# kontrol_v2.net
KiCad netlist of a schematic drawn in EAGLE
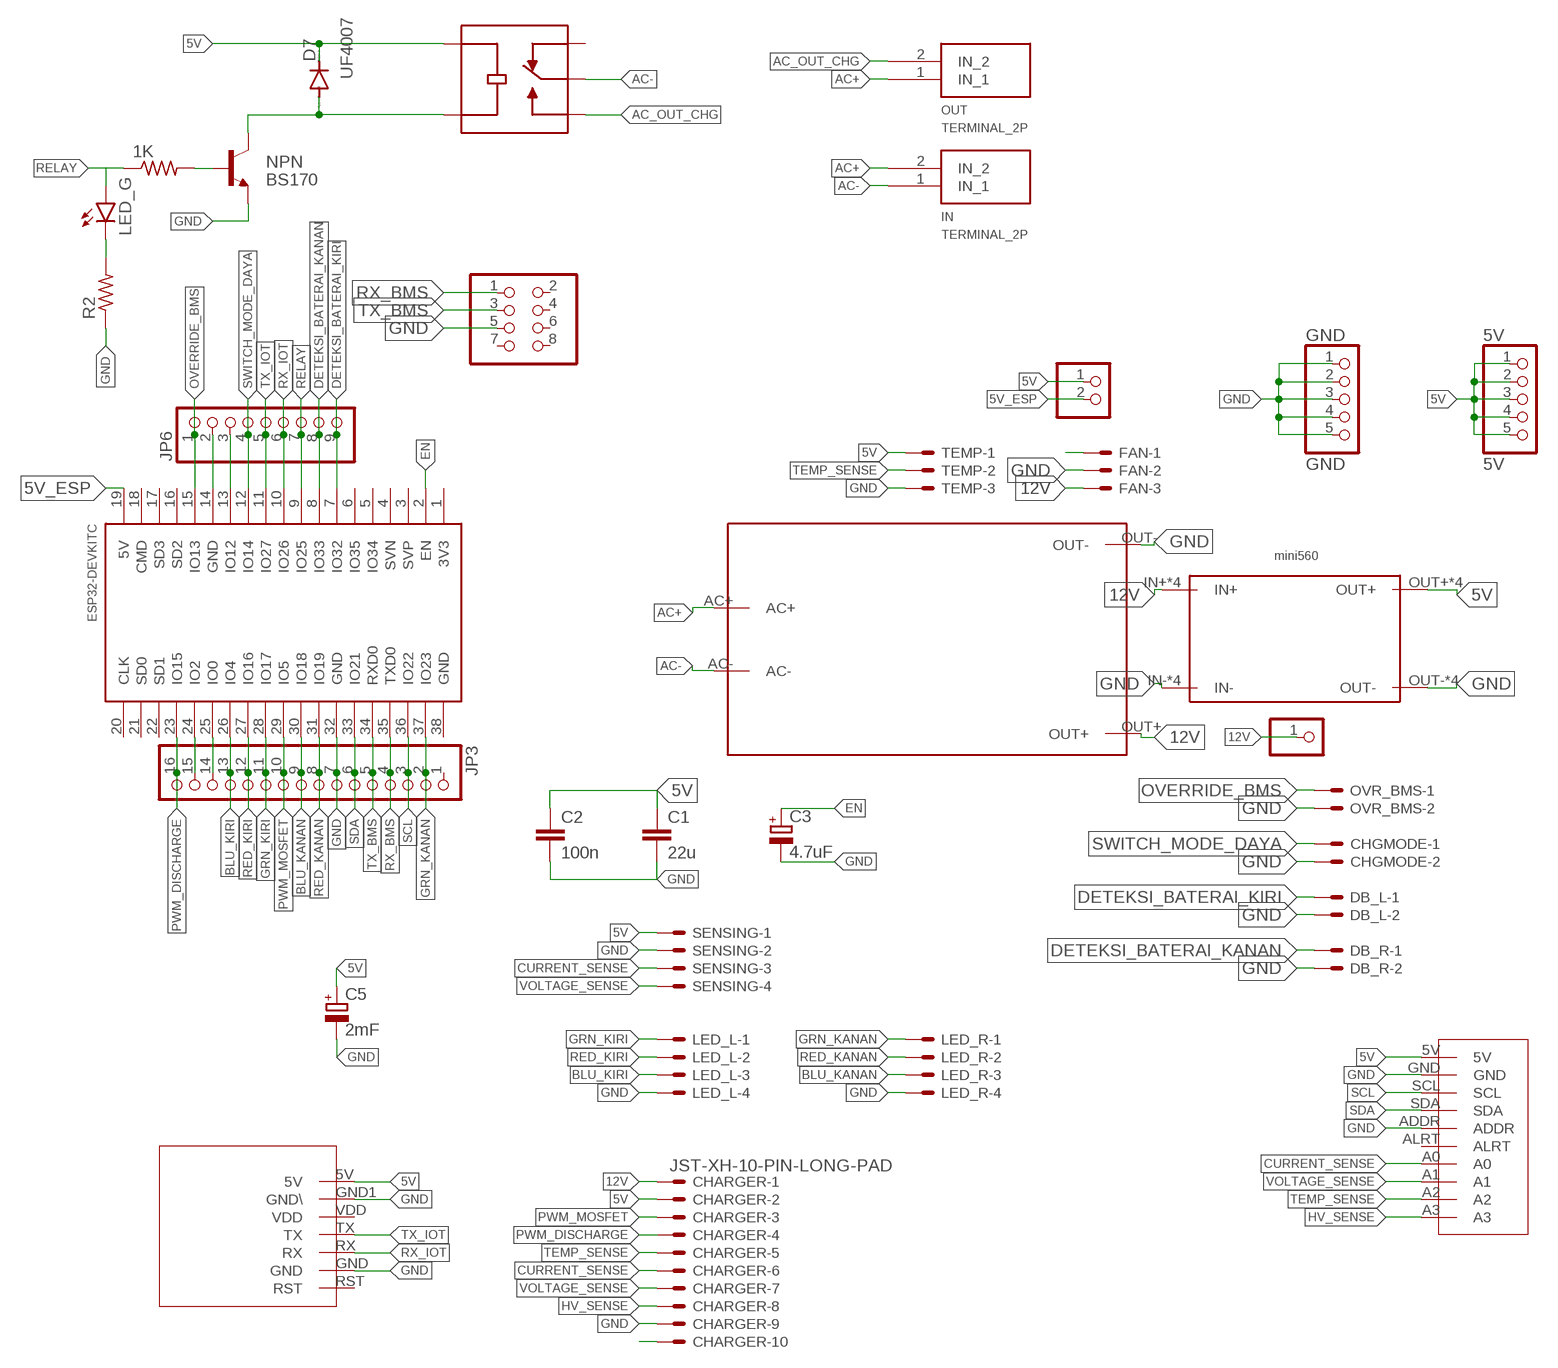
[diagram p0: schematic, sheet 1]

(export (version "E")
  (design (tool "Eeschema 10.0.6"))
  (components
    (comp (ref "1K")
      (value "1k")
      (footprint "eagle-import:0204_7")
      (libsource (lib "eagle-import") (part "R-US_0204/7"))
    )
    (comp (ref "5V")
      (value "5V")
      (footprint "eagle-import:1X05")
      (libsource (lib "eagle-import") (part "PINHD-1X5"))
    )
    (comp (ref "C1")
      (value "22u")
      (footprint "eagle-import:C2.5-5")
      (libsource (lib "eagle-import") (part "C2.5/5"))
    )
    (comp (ref "C2")
      (value "100n")
      (footprint "eagle-import:C2.5-6")
      (libsource (lib "eagle-import") (part "C2.5/6"))
    )
    (comp (ref "C3")
      (value "4.7uF")
      (footprint "eagle-import:E2,5-6E")
      (libsource (lib "eagle-import") (part "CPOL-EUE2,5-6E"))
    )
    (comp (ref "C5")
      (value "2mF")
      (footprint "eagle-import:E3,5-10")
      (libsource (lib "eagle-import") (part "CPOL-EUE3.5-10"))
    )
    (comp (ref "CHARGER")
      (value "JST-XH-10-PIN-LONG-PAD")
      (footprint "eagle-import:JST-XH-10-PACKAGE-LONG-PAD")
      (libsource (lib "eagle-import") (part "JST-XH-10-PIN-LONG-PAD"))
    )
    (comp (ref "CHGMODE")
      (value "JST-XH-02-PIN-LONG-PAD")
      (footprint "eagle-import:JST-XH-02-PACKAGE-LONG-PAD")
      (libsource (lib "eagle-import") (part "JST-XH-02-PIN-LONG-PAD"))
    )
    (comp (ref "D4")
      (value "LED_G")
      (footprint "eagle-import:LED_5MM")
      (libsource (lib "eagle-import") (part "LED5MM"))
    )
    (comp (ref "D7")
      (value "UF4007")
      (footprint "eagle-import:DO34-7")
      (libsource (lib "eagle-import") (part "BAS15"))
    )
    (comp (ref "DB_L")
      (value "JST-XH-02-PIN-LONG-PAD")
      (footprint "eagle-import:JST-XH-02-PACKAGE-LONG-PAD")
      (libsource (lib "eagle-import") (part "JST-XH-02-PIN-LONG-PAD"))
    )
    (comp (ref "DB_R")
      (value "JST-XH-02-PIN-LONG-PAD")
      (footprint "eagle-import:JST-XH-02-PACKAGE-LONG-PAD")
      (libsource (lib "eagle-import") (part "JST-XH-02-PIN-LONG-PAD"))
    )
    (comp (ref "FAN")
      (value "JST-XH-03-PIN-LONG-PAD")
      (footprint "eagle-import:JST-XH-03-PACKAGE-LONG-PAD")
      (libsource (lib "eagle-import") (part "JST-XH-03-PIN-LONG-PAD"))
    )
    (comp (ref "GND")
      (value "GND")
      (footprint "eagle-import:1X05")
      (libsource (lib "eagle-import") (part "PINHD-1X5"))
    )
    (comp (ref "HI_LINK1")
      (value "HI_LINK")
      (footprint "eagle-import:HI_LINK")
      (libsource (lib "eagle-import") (part "HI_LINK"))
    )
    (comp (ref "IN")
      (value "TERMINAL_2P")
      (footprint "eagle-import:TERMINAL_2P")
      (libsource (lib "eagle-import") (part "TERMINAL_2P"))
    )
    (comp (ref "JP2")
      (value "PINHD-2X4")
      (footprint "eagle-import:2X04")
      (libsource (lib "eagle-import") (part "PINHD-2X4"))
    )
    (comp (ref "JP3")
      (value "PINHD-1X16")
      (footprint "eagle-import:1X16")
      (libsource (lib "eagle-import") (part "PINHD-1X16"))
    )
    (comp (ref "JP4")
      (value "PINHD-1X1")
      (footprint "eagle-import:1X01")
      (libsource (lib "eagle-import") (part "PINHD-1X1"))
    )
    (comp (ref "JP6")
      (value "PINHD-1X9")
      (footprint "eagle-import:1X09")
      (libsource (lib "eagle-import") (part "PINHD-1X9"))
    )
    (comp (ref "JP7")
      (value "PINHD-1X2")
      (footprint "eagle-import:1X02")
      (libsource (lib "eagle-import") (part "PINHD-1X2"))
    )
    (comp (ref "K1")
      (value "SRD-12VDC-SL-C")
      (footprint "eagle-import:RELAY_SRD-12VDC-SL-C")
      (fields (field (name "MF") "Songle Relay"))
      (libsource (lib "eagle-import") (part "SRD-12VDC-SL-C"))
    )
    (comp (ref "LED_L")
      (value "JST-XH-04-PIN-LONG-PAD")
      (footprint "eagle-import:JST-XH-04-PACKAGE-LONG-PAD")
      (libsource (lib "eagle-import") (part "JST-XH-04-PIN-LONG-PAD"))
    )
    (comp (ref "LED_R")
      (value "JST-XH-04-PIN-LONG-PAD")
      (footprint "eagle-import:JST-XH-04-PACKAGE-LONG-PAD")
      (libsource (lib "eagle-import") (part "JST-XH-04-PIN-LONG-PAD"))
    )
    (comp (ref "MINI1")
      (value "MINI560")
      (footprint "eagle-import:MINI560")
      (libsource (lib "eagle-import") (part "MINI560"))
    )
    (comp (ref "NPN")
      (value "BS170")
      (footprint "eagle-import:TO92-CBE")
      (libsource (lib "eagle-import") (part "-NPN-TO92-CBEBC547A"))
    )
    (comp (ref "OUT")
      (value "TERMINAL_2P")
      (footprint "eagle-import:TERMINAL_2P")
      (libsource (lib "eagle-import") (part "TERMINAL_2P"))
    )
    (comp (ref "OVR_BMS")
      (value "JST-XH-02-PIN-LONG-PAD")
      (footprint "eagle-import:JST-XH-02-PACKAGE-LONG-PAD")
      (libsource (lib "eagle-import") (part "JST-XH-02-PIN-LONG-PAD"))
    )
    (comp (ref "R2")
      (value "6k")
      (footprint "eagle-import:0204_7")
      (libsource (lib "eagle-import") (part "R-US_0204/7"))
    )
    (comp (ref "SENSING")
      (value "JST-XH-04-PIN-LONG-PAD")
      (footprint "eagle-import:JST-XH-04-PACKAGE-LONG-PAD")
      (libsource (lib "eagle-import") (part "JST-XH-04-PIN-LONG-PAD"))
    )
    (comp (ref "TEMP")
      (value "JST-XH-03-PIN-LONG-PAD")
      (footprint "eagle-import:JST-XH-03-PACKAGE-LONG-PAD")
      (libsource (lib "eagle-import") (part "JST-XH-03-PIN-LONG-PAD"))
    )
    (comp (ref "U$1")
      (value "ESP32DEVKITC")
      (footprint "eagle-import:ESP32-DEVKITC")
      (libsource (lib "eagle-import") (part "ESP32DEVKITC"))
    )
    (comp (ref "U$2")
      (value "ADS1115")
      (footprint "eagle-import:ADS1115")
      (libsource (lib "eagle-import") (part "ADS1115"))
    )
    (comp (ref "U$3")
      (value "SIM800V2")
      (footprint "eagle-import:SIM800V2")
      (libsource (lib "eagle-import") (part "SIM800V2"))
    )
  )
  (nets
    (net (code "1") (name "5V") (class "Default")
      (node (ref "5V") (pin "1") (pinfunction "1_1") (pintype "passive"))
      (node (ref "5V") (pin "2") (pinfunction "2_2") (pintype "passive"))
      (node (ref "5V") (pin "3") (pinfunction "3_3") (pintype "passive"))
      (node (ref "5V") (pin "4") (pinfunction "4_4") (pintype "passive"))
      (node (ref "5V") (pin "5") (pinfunction "5_5") (pintype "passive"))
      (node (ref "C1") (pin "1") (pinfunction "1_1") (pintype "passive"))
      (node (ref "C2") (pin "1") (pinfunction "1_1") (pintype "passive"))
      (node (ref "C5") (pin "+") (pinfunction "+_+") (pintype "passive"))
      (node (ref "CHARGER") (pin "2") (pinfunction "S_2") (pintype "passive"))
      (node (ref "D7") (pin "C") (pinfunction "C_C") (pintype "passive"))
      (node (ref "JP7") (pin "1") (pinfunction "1_1") (pintype "passive"))
      (node (ref "K1") (pin "COIL1") (pinfunction "COIL1_COIL1") (pintype "passive"))
      (node (ref "MINI1") (pin "OUT+") (pinfunction "OUT+_OUT+") (pintype "bidirectional"))
      (node (ref "MINI1") (pin "OUT+1") (pinfunction "OUT+_OUT+1") (pintype "bidirectional"))
      (node (ref "MINI1") (pin "OUT+2") (pinfunction "OUT+_OUT+2") (pintype "bidirectional"))
      (node (ref "MINI1") (pin "OUT+3") (pinfunction "OUT+_OUT+3") (pintype "bidirectional"))
      (node (ref "SENSING") (pin "1") (pinfunction "S_1") (pintype "passive"))
      (node (ref "TEMP") (pin "1") (pinfunction "S_1") (pintype "passive"))
      (node (ref "U$2") (pin "5V") (pinfunction "5V_5V") (pintype "bidirectional"))
      (node (ref "U$3") (pin "5V") (pinfunction "5V_5V") (pintype "bidirectional"))
    )
    (net (code "2") (name "5V_ESP") (class "Default")
      (node (ref "JP7") (pin "2") (pinfunction "2_2") (pintype "passive"))
      (node (ref "U$1") (pin "19") (pinfunction "5V_19") (pintype "bidirectional"))
    )
    (net (code "3") (name "12V") (class "Default")
      (node (ref "CHARGER") (pin "1") (pinfunction "S_1") (pintype "passive"))
      (node (ref "FAN") (pin "3") (pinfunction "S_3") (pintype "passive"))
      (node (ref "HI_LINK1") (pin "OUT+") (pinfunction "OUT+_OUT+") (pintype "bidirectional"))
      (node (ref "JP4") (pin "1") (pinfunction "1_1") (pintype "passive"))
      (node (ref "MINI1") (pin "IN+") (pinfunction "IN+_IN+") (pintype "bidirectional"))
      (node (ref "MINI1") (pin "IN+1") (pinfunction "IN+_IN+1") (pintype "bidirectional"))
      (node (ref "MINI1") (pin "IN+2") (pinfunction "IN+_IN+2") (pintype "bidirectional"))
      (node (ref "MINI1") (pin "IN+3") (pinfunction "IN+_IN+3") (pintype "bidirectional"))
    )
    (net (code "4") (name "AC+") (class "Default")
      (node (ref "HI_LINK1") (pin "AC+") (pinfunction "AC+_AC+") (pintype "bidirectional"))
      (node (ref "IN") (pin "2") (pinfunction "IN_2_2") (pintype "bidirectional"))
      (node (ref "OUT") (pin "1") (pinfunction "IN_1_1") (pintype "bidirectional"))
    )
    (net (code "5") (name "AC-") (class "Default")
      (node (ref "HI_LINK1") (pin "AC-") (pinfunction "AC-_AC-") (pintype "bidirectional"))
      (node (ref "IN") (pin "1") (pinfunction "IN_1_1") (pintype "bidirectional"))
      (node (ref "K1") (pin "COM") (pinfunction "COM_COM") (pintype "passive"))
    )
    (net (code "6") (name "AC_OUT_CHG") (class "Default")
      (node (ref "K1") (pin "NO") (pinfunction "NO_NO") (pintype "passive"))
      (node (ref "OUT") (pin "2") (pinfunction "IN_2_2") (pintype "bidirectional"))
    )
    (net (code "7") (name "BLU_KANAN") (class "Default")
      (node (ref "JP3") (pin "9") (pinfunction "9_9") (pintype "passive"))
      (node (ref "LED_R") (pin "3") (pinfunction "S_3") (pintype "passive"))
      (node (ref "U$1") (pin "30") (pinfunction "IO18_30") (pintype "bidirectional"))
    )
    (net (code "8") (name "BLU_KIRI") (class "Default")
      (node (ref "JP3") (pin "13") (pinfunction "13_13") (pintype "passive"))
      (node (ref "LED_L") (pin "3") (pinfunction "S_3") (pintype "passive"))
      (node (ref "U$1") (pin "26") (pinfunction "IO4_26") (pintype "bidirectional"))
    )
    (net (code "9") (name "CURRENT_SENSE") (class "Default")
      (node (ref "CHARGER") (pin "6") (pinfunction "S_6") (pintype "passive"))
      (node (ref "SENSING") (pin "3") (pinfunction "S_3") (pintype "passive"))
      (node (ref "U$2") (pin "A0") (pinfunction "A0_A0") (pintype "bidirectional"))
    )
    (net (code "10") (name "DETEKSI_BATERAI_KANAN") (class "Default")
      (node (ref "DB_R") (pin "1") (pinfunction "S_1") (pintype "passive"))
      (node (ref "JP6") (pin "8") (pinfunction "8_8") (pintype "passive"))
      (node (ref "U$1") (pin "8") (pinfunction "IO33_8") (pintype "bidirectional"))
    )
    (net (code "11") (name "DETEKSI_BATERAI_KIRI") (class "Default")
      (node (ref "DB_L") (pin "1") (pinfunction "S_1") (pintype "passive"))
      (node (ref "JP6") (pin "9") (pinfunction "9_9") (pintype "passive"))
      (node (ref "U$1") (pin "7") (pinfunction "IO32_7") (pintype "bidirectional"))
    )
    (net (code "12") (name "EN") (class "Default")
      (node (ref "C3") (pin "+") (pinfunction "+_+") (pintype "passive"))
      (node (ref "U$1") (pin "2") (pinfunction "EN_2") (pintype "bidirectional"))
    )
    (net (code "13") (name "GND") (class "Default")
      (node (ref "C1") (pin "2") (pinfunction "2_2") (pintype "passive"))
      (node (ref "C2") (pin "2") (pinfunction "2_2") (pintype "passive"))
      (node (ref "C3") (pin "-") (pinfunction "-_-") (pintype "passive"))
      (node (ref "C5") (pin "-") (pinfunction "-_-") (pintype "passive"))
      (node (ref "CHARGER") (pin "9") (pinfunction "S_9") (pintype "passive"))
      (node (ref "CHGMODE") (pin "2") (pinfunction "S_2") (pintype "passive"))
      (node (ref "DB_L") (pin "2") (pinfunction "S_2") (pintype "passive"))
      (node (ref "DB_R") (pin "2") (pinfunction "S_2") (pintype "passive"))
      (node (ref "FAN") (pin "2") (pinfunction "S_2") (pintype "passive"))
      (node (ref "GND") (pin "1") (pinfunction "1_1") (pintype "passive"))
      (node (ref "GND") (pin "2") (pinfunction "2_2") (pintype "passive"))
      (node (ref "GND") (pin "3") (pinfunction "3_3") (pintype "passive"))
      (node (ref "GND") (pin "4") (pinfunction "4_4") (pintype "passive"))
      (node (ref "GND") (pin "5") (pinfunction "5_5") (pintype "passive"))
      (node (ref "HI_LINK1") (pin "OUT-") (pinfunction "OUT-_OUT-") (pintype "bidirectional"))
      (node (ref "JP2") (pin "5") (pinfunction "5_5") (pintype "passive"))
      (node (ref "JP3") (pin "7") (pinfunction "7_7") (pintype "passive"))
      (node (ref "LED_L") (pin "4") (pinfunction "S_4") (pintype "passive"))
      (node (ref "LED_R") (pin "4") (pinfunction "S_4") (pintype "passive"))
      (node (ref "MINI1") (pin "IN-") (pinfunction "IN-_IN-") (pintype "bidirectional"))
      (node (ref "MINI1") (pin "IN-1") (pinfunction "IN-_IN-1") (pintype "bidirectional"))
      (node (ref "MINI1") (pin "IN-2") (pinfunction "IN-_IN-2") (pintype "bidirectional"))
      (node (ref "MINI1") (pin "IN-3") (pinfunction "IN-_IN-3") (pintype "bidirectional"))
      (node (ref "MINI1") (pin "OUT-") (pinfunction "OUT-_OUT-") (pintype "bidirectional"))
      (node (ref "MINI1") (pin "OUT-1") (pinfunction "OUT-_OUT-1") (pintype "bidirectional"))
      (node (ref "MINI1") (pin "OUT-2") (pinfunction "OUT-_OUT-2") (pintype "bidirectional"))
      (node (ref "MINI1") (pin "OUT-3") (pinfunction "OUT-_OUT-3") (pintype "bidirectional"))
      (node (ref "NPN") (pin "E") (pinfunction "E_E") (pintype "passive"))
      (node (ref "OVR_BMS") (pin "2") (pinfunction "S_2") (pintype "passive"))
      (node (ref "R2") (pin "1") (pinfunction "1_1") (pintype "passive"))
      (node (ref "SENSING") (pin "2") (pinfunction "S_2") (pintype "passive"))
      (node (ref "TEMP") (pin "3") (pinfunction "S_3") (pintype "passive"))
      (node (ref "U$1") (pin "32") (pinfunction "GND_32") (pintype "bidirectional"))
      (node (ref "U$2") (pin "ADDR") (pinfunction "ADDR_ADDR") (pintype "bidirectional"))
      (node (ref "U$2") (pin "GND") (pinfunction "GND_GND") (pintype "bidirectional"))
      (node (ref "U$3") (pin "GND") (pinfunction "GND_GND") (pintype "bidirectional"))
      (node (ref "U$3") (pin "GND1") (pinfunction "GND\\_GND1") (pintype "bidirectional"))
    )
    (net (code "14") (name "GRN_KANAN") (class "Default")
      (node (ref "JP3") (pin "2") (pinfunction "2_2") (pintype "passive"))
      (node (ref "LED_R") (pin "1") (pinfunction "S_1") (pintype "passive"))
      (node (ref "U$1") (pin "37") (pinfunction "IO23_37") (pintype "bidirectional"))
    )
    (net (code "15") (name "GRN_KIRI") (class "Default")
      (node (ref "JP3") (pin "11") (pinfunction "11_11") (pintype "passive"))
      (node (ref "LED_L") (pin "1") (pinfunction "S_1") (pintype "passive"))
      (node (ref "U$1") (pin "28") (pinfunction "IO17_28") (pintype "bidirectional"))
    )
    (net (code "16") (name "HV_SENSE") (class "Default")
      (node (ref "CHARGER") (pin "8") (pinfunction "S_8") (pintype "passive"))
      (node (ref "U$2") (pin "A3") (pinfunction "A3_A3") (pintype "bidirectional"))
    )
    (net (code "17") (name "Net-(1K-Pad2)") (class "Default")
      (node (ref "1K") (pin "2") (pinfunction "2_2") (pintype "passive"))
      (node (ref "NPN") (pin "B") (pinfunction "B_B") (pintype "passive"))
    )
    (net (code "18") (name "Net-(D4-C)") (class "Default")
      (node (ref "D4") (pin "K") (pinfunction "C_K") (pintype "passive"))
      (node (ref "R2") (pin "2") (pinfunction "2_2") (pintype "passive"))
    )
    (net (code "19") (name "Net-(D7-PadA)") (class "Default")
      (node (ref "D7") (pin "A") (pinfunction "A_A") (pintype "passive"))
      (node (ref "K1") (pin "COIL2") (pinfunction "COIL2_COIL2") (pintype "passive"))
      (node (ref "NPN") (pin "C") (pinfunction "C_C") (pintype "passive"))
    )
    (net (code "20") (name "Net-(JP6-Pad2)") (class "Default")
      (node (ref "JP6") (pin "2") (pinfunction "2_2") (pintype "passive"))
      (node (ref "U$1") (pin "14") (pinfunction "GND_14") (pintype "bidirectional"))
    )
    (net (code "21") (name "Net-(U$1-IO0)") (class "Default")
      (node (ref "JP3") (pin "14") (pinfunction "14_14") (pintype "passive"))
      (node (ref "U$1") (pin "25") (pinfunction "IO0_25") (pintype "bidirectional"))
    )
    (net (code "22") (name "Net-(U$1-IO2)") (class "Default")
      (node (ref "JP3") (pin "15") (pinfunction "15_15") (pintype "passive"))
      (node (ref "U$1") (pin "24") (pinfunction "IO2_24") (pintype "bidirectional"))
    )
    (net (code "23") (name "Net-(U$1-IO12)") (class "Default")
      (node (ref "JP6") (pin "3") (pinfunction "3_3") (pintype "passive"))
      (node (ref "U$1") (pin "13") (pinfunction "IO12_13") (pintype "bidirectional"))
    )
    (net (code "24") (name "OVERRIDE_BMS") (class "Default")
      (node (ref "JP6") (pin "1") (pinfunction "1_1") (pintype "passive"))
      (node (ref "OVR_BMS") (pin "1") (pinfunction "S_1") (pintype "passive"))
      (node (ref "U$1") (pin "15") (pinfunction "IO13_15") (pintype "bidirectional"))
    )
    (net (code "25") (name "PWM_DISCHARGE") (class "Default")
      (node (ref "CHARGER") (pin "4") (pinfunction "S_4") (pintype "passive"))
      (node (ref "JP3") (pin "16") (pinfunction "16_16") (pintype "passive"))
      (node (ref "U$1") (pin "23") (pinfunction "IO15_23") (pintype "bidirectional"))
    )
    (net (code "26") (name "PWM_MOSFET") (class "Default")
      (node (ref "CHARGER") (pin "3") (pinfunction "S_3") (pintype "passive"))
      (node (ref "JP3") (pin "10") (pinfunction "10_10") (pintype "passive"))
      (node (ref "U$1") (pin "29") (pinfunction "IO5_29") (pintype "bidirectional"))
    )
    (net (code "27") (name "RED_KANAN") (class "Default")
      (node (ref "JP3") (pin "8") (pinfunction "8_8") (pintype "passive"))
      (node (ref "LED_R") (pin "2") (pinfunction "S_2") (pintype "passive"))
      (node (ref "U$1") (pin "31") (pinfunction "IO19_31") (pintype "bidirectional"))
    )
    (net (code "28") (name "RED_KIRI") (class "Default")
      (node (ref "JP3") (pin "12") (pinfunction "12_12") (pintype "passive"))
      (node (ref "LED_L") (pin "2") (pinfunction "S_2") (pintype "passive"))
      (node (ref "U$1") (pin "27") (pinfunction "IO16_27") (pintype "bidirectional"))
    )
    (net (code "29") (name "RELAY") (class "Default")
      (node (ref "1K") (pin "1") (pinfunction "1_1") (pintype "passive"))
      (node (ref "D4") (pin "A") (pinfunction "A_A") (pintype "passive"))
      (node (ref "JP6") (pin "7") (pinfunction "7_7") (pintype "passive"))
      (node (ref "U$1") (pin "9") (pinfunction "IO25_9") (pintype "bidirectional"))
    )
    (net (code "30") (name "RX_BMS") (class "Default")
      (node (ref "JP2") (pin "1") (pinfunction "1_1") (pintype "passive"))
      (node (ref "JP3") (pin "4") (pinfunction "4_4") (pintype "passive"))
      (node (ref "U$1") (pin "35") (pinfunction "TXD0_35") (pintype "bidirectional"))
    )
    (net (code "31") (name "RX_IOT") (class "Default")
      (node (ref "JP6") (pin "6") (pinfunction "6_6") (pintype "passive"))
      (node (ref "U$1") (pin "10") (pinfunction "IO26_10") (pintype "bidirectional"))
      (node (ref "U$3") (pin "RX") (pinfunction "RX_RX") (pintype "bidirectional"))
    )
    (net (code "32") (name "SCL") (class "Default")
      (node (ref "JP3") (pin "3") (pinfunction "3_3") (pintype "passive"))
      (node (ref "U$1") (pin "36") (pinfunction "IO22_36") (pintype "bidirectional"))
      (node (ref "U$2") (pin "SCL") (pinfunction "SCL_SCL") (pintype "bidirectional"))
    )
    (net (code "33") (name "SDA") (class "Default")
      (node (ref "JP3") (pin "6") (pinfunction "6_6") (pintype "passive"))
      (node (ref "U$1") (pin "33") (pinfunction "IO21_33") (pintype "bidirectional"))
      (node (ref "U$2") (pin "SDA") (pinfunction "SDA_SDA") (pintype "bidirectional"))
    )
    (net (code "34") (name "SWITCH_MODE_DAYA") (class "Default")
      (node (ref "CHGMODE") (pin "1") (pinfunction "S_1") (pintype "passive"))
      (node (ref "JP6") (pin "4") (pinfunction "4_4") (pintype "passive"))
      (node (ref "U$1") (pin "12") (pinfunction "IO14_12") (pintype "bidirectional"))
    )
    (net (code "35") (name "TEMP_SENSE") (class "Default")
      (node (ref "CHARGER") (pin "5") (pinfunction "S_5") (pintype "passive"))
      (node (ref "TEMP") (pin "2") (pinfunction "S_2") (pintype "passive"))
      (node (ref "U$2") (pin "A2") (pinfunction "A2_A2") (pintype "bidirectional"))
    )
    (net (code "36") (name "TX_BMS") (class "Default")
      (node (ref "JP2") (pin "3") (pinfunction "3_3") (pintype "passive"))
      (node (ref "JP3") (pin "5") (pinfunction "5_5") (pintype "passive"))
      (node (ref "U$1") (pin "34") (pinfunction "RXD0_34") (pintype "bidirectional"))
    )
    (net (code "37") (name "TX_IOT") (class "Default")
      (node (ref "JP6") (pin "5") (pinfunction "5_5") (pintype "passive"))
      (node (ref "U$1") (pin "11") (pinfunction "IO27_11") (pintype "bidirectional"))
      (node (ref "U$3") (pin "TX") (pinfunction "TX_TX") (pintype "bidirectional"))
    )
    (net (code "38") (name "VOLTAGE_SENSE") (class "Default")
      (node (ref "CHARGER") (pin "7") (pinfunction "S_7") (pintype "passive"))
      (node (ref "SENSING") (pin "4") (pinfunction "S_4") (pintype "passive"))
      (node (ref "U$2") (pin "A1") (pinfunction "A1_A1") (pintype "bidirectional"))
    )
    (net (code "39") (name "unconnected-(CHARGERB-S-Pad10)") (class "Default")
      (node (ref "CHARGER") (pin "10") (pinfunction "S_10") (pintype "passive"))
    )
    (net (code "40") (name "unconnected-(FANA-S-Pad1)") (class "Default")
      (node (ref "FAN") (pin "1") (pinfunction "S_1") (pintype "passive"))
    )
    (net (code "41") (name "unconnected-(JP2-Pad2)") (class "Default")
      (node (ref "JP2") (pin "2") (pinfunction "2_2") (pintype "passive"))
    )
    (net (code "42") (name "unconnected-(JP2-Pad4)") (class "Default")
      (node (ref "JP2") (pin "4") (pinfunction "4_4") (pintype "passive"))
    )
    (net (code "43") (name "unconnected-(JP2-Pad6)") (class "Default")
      (node (ref "JP2") (pin "6") (pinfunction "6_6") (pintype "passive"))
    )
    (net (code "44") (name "unconnected-(JP2-Pad7)") (class "Default")
      (node (ref "JP2") (pin "7") (pinfunction "7_7") (pintype "passive"))
    )
    (net (code "45") (name "unconnected-(JP2-Pad8)") (class "Default")
      (node (ref "JP2") (pin "8") (pinfunction "8_8") (pintype "passive"))
    )
    (net (code "46") (name "unconnected-(JP3-Pad1)") (class "Default")
      (node (ref "JP3") (pin "1") (pinfunction "1_1") (pintype "passive"))
    )
    (net (code "47") (name "unconnected-(K1-PadNC)") (class "Default")
      (node (ref "K1") (pin "NC") (pinfunction "NC_NC") (pintype "passive"))
    )
    (net (code "48") (name "unconnected-(U$1-3V3-Pad1)") (class "Default")
      (node (ref "U$1") (pin "1") (pinfunction "3V3_1") (pintype "bidirectional"))
    )
    (net (code "49") (name "unconnected-(U$1-CLK-Pad20)") (class "Default")
      (node (ref "U$1") (pin "20") (pinfunction "CLK_20") (pintype "bidirectional"))
    )
    (net (code "50") (name "unconnected-(U$1-CMD-Pad18)") (class "Default")
      (node (ref "U$1") (pin "18") (pinfunction "CMD_18") (pintype "bidirectional"))
    )
    (net (code "51") (name "unconnected-(U$1-GND-Pad38)") (class "Default")
      (node (ref "U$1") (pin "38") (pinfunction "GND_38") (pintype "bidirectional"))
    )
    (net (code "52") (name "unconnected-(U$1-IO34-Pad5)") (class "Default")
      (node (ref "U$1") (pin "5") (pinfunction "IO34_5") (pintype "bidirectional"))
    )
    (net (code "53") (name "unconnected-(U$1-IO35-Pad6)") (class "Default")
      (node (ref "U$1") (pin "6") (pinfunction "IO35_6") (pintype "bidirectional"))
    )
    (net (code "54") (name "unconnected-(U$1-SD0-Pad21)") (class "Default")
      (node (ref "U$1") (pin "21") (pinfunction "SD0_21") (pintype "bidirectional"))
    )
    (net (code "55") (name "unconnected-(U$1-SD1-Pad22)") (class "Default")
      (node (ref "U$1") (pin "22") (pinfunction "SD1_22") (pintype "bidirectional"))
    )
    (net (code "56") (name "unconnected-(U$1-SD2-Pad16)") (class "Default")
      (node (ref "U$1") (pin "16") (pinfunction "SD2_16") (pintype "bidirectional"))
    )
    (net (code "57") (name "unconnected-(U$1-SD3-Pad17)") (class "Default")
      (node (ref "U$1") (pin "17") (pinfunction "SD3_17") (pintype "bidirectional"))
    )
    (net (code "58") (name "unconnected-(U$1-SVN-Pad4)") (class "Default")
      (node (ref "U$1") (pin "4") (pinfunction "SVN_4") (pintype "bidirectional"))
    )
    (net (code "59") (name "unconnected-(U$1-SVP-Pad3)") (class "Default")
      (node (ref "U$1") (pin "3") (pinfunction "SVP_3") (pintype "bidirectional"))
    )
    (net (code "60") (name "unconnected-(U$2-PadALRT)") (class "Default")
      (node (ref "U$2") (pin "ALRT") (pinfunction "ALRT_ALRT") (pintype "bidirectional"))
    )
    (net (code "61") (name "unconnected-(U$3-PadRST)") (class "Default")
      (node (ref "U$3") (pin "RST") (pinfunction "RST_RST") (pintype "bidirectional"))
    )
    (net (code "62") (name "unconnected-(U$3-PadVDD)") (class "Default")
      (node (ref "U$3") (pin "VDD") (pinfunction "VDD_VDD") (pintype "bidirectional"))
    )
  )
)
